# Adafruit_AD849x_Thermo.net
KiCad netlist of a schematic drawn in EAGLE
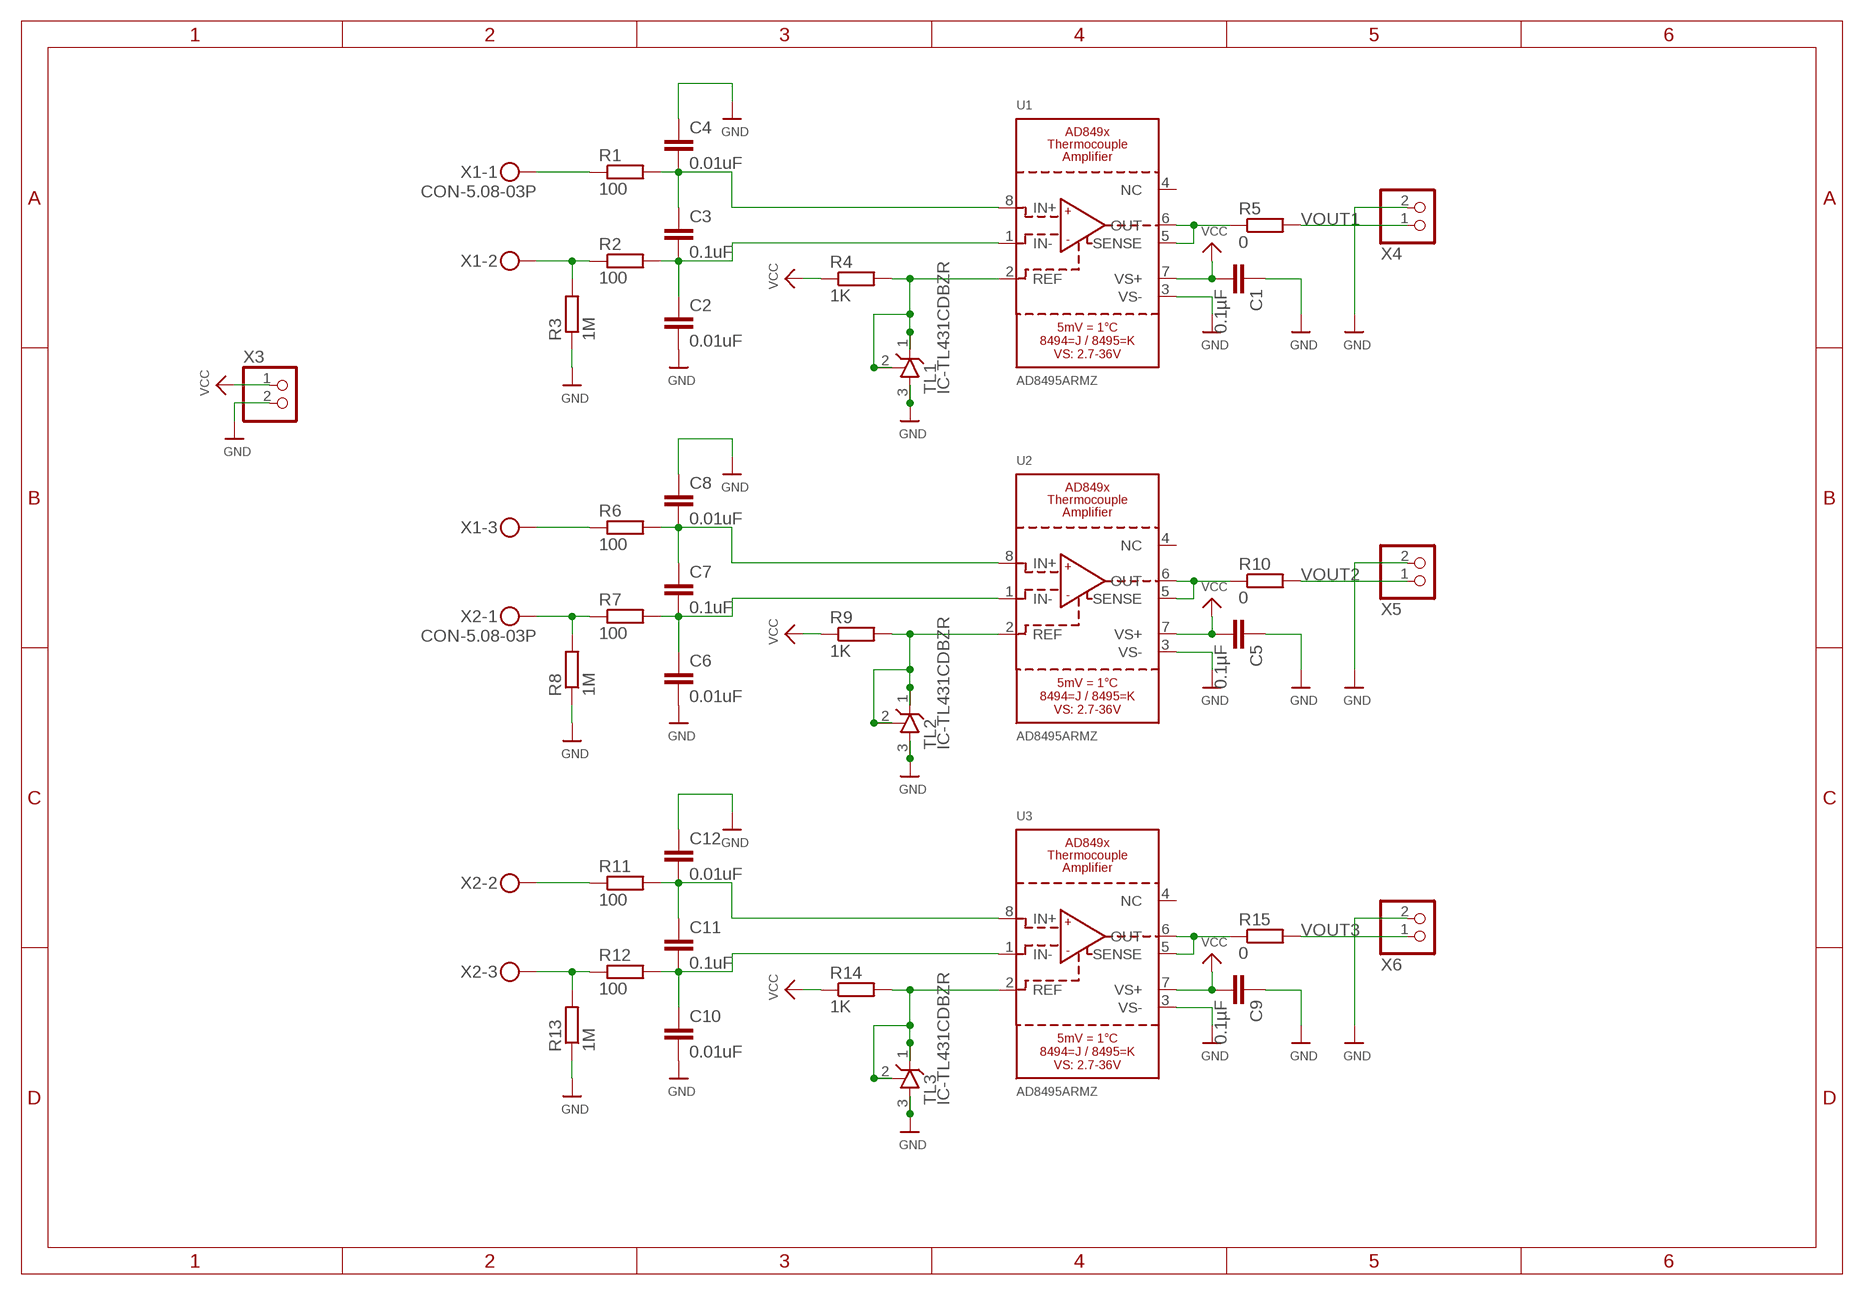
[diagram p0: schematic, sheet 1]

(export (version "E")
  (design (tool "Eeschema 10.0.6"))
  (components
    (comp (ref "C1")
      (value "0.1µF")
      (footprint "eagle-import:C0805")
      (libsource (lib "eagle-import") (part "CAP_0805"))
    )
    (comp (ref "C2")
      (value "0.01uF")
      (footprint "eagle-import:C0805")
      (libsource (lib "eagle-import") (part "CAP_0805"))
    )
    (comp (ref "C3")
      (value "0.1uF")
      (footprint "eagle-import:C0805")
      (libsource (lib "eagle-import") (part "CAP_0805"))
    )
    (comp (ref "C4")
      (value "0.01uF")
      (footprint "eagle-import:C0805")
      (libsource (lib "eagle-import") (part "CAP_0805"))
    )
    (comp (ref "C5")
      (value "0.1µF")
      (footprint "eagle-import:C0805")
      (libsource (lib "eagle-import") (part "CAP_0805"))
    )
    (comp (ref "C6")
      (value "0.01uF")
      (footprint "eagle-import:C0805")
      (libsource (lib "eagle-import") (part "CAP_0805"))
    )
    (comp (ref "C7")
      (value "0.1uF")
      (footprint "eagle-import:C0805")
      (libsource (lib "eagle-import") (part "CAP_0805"))
    )
    (comp (ref "C8")
      (value "0.01uF")
      (footprint "eagle-import:C0805")
      (libsource (lib "eagle-import") (part "CAP_0805"))
    )
    (comp (ref "C9")
      (value "0.1µF")
      (footprint "eagle-import:C0805")
      (libsource (lib "eagle-import") (part "CAP_0805"))
    )
    (comp (ref "C10")
      (value "0.01uF")
      (footprint "eagle-import:C0805")
      (libsource (lib "eagle-import") (part "CAP_0805"))
    )
    (comp (ref "C11")
      (value "0.1uF")
      (footprint "eagle-import:C0805")
      (libsource (lib "eagle-import") (part "CAP_0805"))
    )
    (comp (ref "C12")
      (value "0.01uF")
      (footprint "eagle-import:C0805")
      (libsource (lib "eagle-import") (part "CAP_0805"))
    )
    (comp (ref "R1")
      (value "100")
      (footprint "eagle-import:R0805")
      (libsource (lib "eagle-import") (part "R_0805"))
    )
    (comp (ref "R2")
      (value "100")
      (footprint "eagle-import:R0805")
      (libsource (lib "eagle-import") (part "R_0805"))
    )
    (comp (ref "R3")
      (value "1M")
      (footprint "eagle-import:R0805")
      (libsource (lib "eagle-import") (part "R_0805"))
    )
    (comp (ref "R4")
      (value "1K")
      (footprint "eagle-import:R0805")
      (libsource (lib "eagle-import") (part "R_0805"))
    )
    (comp (ref "R5")
      (value "0")
      (footprint "eagle-import:R0805")
      (libsource (lib "eagle-import") (part "R_0805"))
    )
    (comp (ref "R6")
      (value "100")
      (footprint "eagle-import:R0805")
      (libsource (lib "eagle-import") (part "R_0805"))
    )
    (comp (ref "R7")
      (value "100")
      (footprint "eagle-import:R0805")
      (libsource (lib "eagle-import") (part "R_0805"))
    )
    (comp (ref "R8")
      (value "1M")
      (footprint "eagle-import:R0805")
      (libsource (lib "eagle-import") (part "R_0805"))
    )
    (comp (ref "R9")
      (value "1K")
      (footprint "eagle-import:R0805")
      (libsource (lib "eagle-import") (part "R_0805"))
    )
    (comp (ref "R10")
      (value "0")
      (footprint "eagle-import:R0805")
      (libsource (lib "eagle-import") (part "R_0805"))
    )
    (comp (ref "R11")
      (value "100")
      (footprint "eagle-import:R0805")
      (libsource (lib "eagle-import") (part "R_0805"))
    )
    (comp (ref "R12")
      (value "100")
      (footprint "eagle-import:R0805")
      (libsource (lib "eagle-import") (part "R_0805"))
    )
    (comp (ref "R13")
      (value "1M")
      (footprint "eagle-import:R0805")
      (libsource (lib "eagle-import") (part "R_0805"))
    )
    (comp (ref "R14")
      (value "1K")
      (footprint "eagle-import:R0805")
      (libsource (lib "eagle-import") (part "R_0805"))
    )
    (comp (ref "R15")
      (value "0")
      (footprint "eagle-import:R0805")
      (libsource (lib "eagle-import") (part "R_0805"))
    )
    (comp (ref "TL1")
      (value "IC-TL431CDBZR")
      (footprint "eagle-import:SOT23")
      (libsource (lib "eagle-import") (part "IC-TL431CDBZR"))
    )
    (comp (ref "TL2")
      (value "IC-TL431CDBZR")
      (footprint "eagle-import:SOT23")
      (libsource (lib "eagle-import") (part "IC-TL431CDBZR"))
    )
    (comp (ref "TL3")
      (value "IC-TL431CDBZR")
      (footprint "eagle-import:SOT23")
      (libsource (lib "eagle-import") (part "IC-TL431CDBZR"))
    )
    (comp (ref "U1")
      (value "AD8495ARMZ")
      (footprint "eagle-import:MSOP8_0.65MM")
      (libsource (lib "eagle-import") (part "AD849X"))
    )
    (comp (ref "U2")
      (value "AD8495ARMZ")
      (footprint "eagle-import:MSOP8_0.65MM")
      (libsource (lib "eagle-import") (part "AD849X"))
    )
    (comp (ref "U3")
      (value "AD8495ARMZ")
      (footprint "eagle-import:MSOP8_0.65MM")
      (libsource (lib "eagle-import") (part "AD849X"))
    )
    (comp (ref "X1")
      (value "CON-5.08-03P")
      (footprint "eagle-import:MKDSN1,5_3-5,08")
      (libsource (lib "eagle-import") (part "CON-5.08-03P"))
    )
    (comp (ref "X2")
      (value "CON-5.08-03P")
      (footprint "eagle-import:MKDSN1,5_3-5,08")
      (libsource (lib "eagle-import") (part "CON-5.08-03P"))
    )
    (comp (ref "X3")
      (value "CON-CP-02")
      (footprint "eagle-import:CON-CT-02")
      (libsource (lib "eagle-import") (part "CON-CP-02"))
    )
    (comp (ref "X4")
      (value "CON-CP-02")
      (footprint "eagle-import:CON-CT-02")
      (libsource (lib "eagle-import") (part "CON-CP-02"))
    )
    (comp (ref "X5")
      (value "CON-CP-02")
      (footprint "eagle-import:CON-CT-02")
      (libsource (lib "eagle-import") (part "CON-CP-02"))
    )
    (comp (ref "X6")
      (value "CON-CP-02")
      (footprint "eagle-import:CON-CT-02")
      (libsource (lib "eagle-import") (part "CON-CP-02"))
    )
  )
  (nets
    (net (code "1") (name "/VOUT1") (class "Default")
      (node (ref "R5") (pin "1") (pinfunction "1_1") (pintype "passive"))
      (node (ref "U1") (pin "5") (pinfunction "SENSE_5") (pintype "bidirectional"))
      (node (ref "U1") (pin "6") (pinfunction "OUT_6") (pintype "output"))
    )
    (net (code "2") (name "/VOUT2") (class "Default")
      (node (ref "R10") (pin "1") (pinfunction "1_1") (pintype "passive"))
      (node (ref "U2") (pin "5") (pinfunction "SENSE_5") (pintype "bidirectional"))
      (node (ref "U2") (pin "6") (pinfunction "OUT_6") (pintype "output"))
    )
    (net (code "3") (name "/VOUT3") (class "Default")
      (node (ref "R15") (pin "1") (pinfunction "1_1") (pintype "passive"))
      (node (ref "U3") (pin "5") (pinfunction "SENSE_5") (pintype "bidirectional"))
      (node (ref "U3") (pin "6") (pinfunction "OUT_6") (pintype "output"))
    )
    (net (code "4") (name "GND") (class "Default")
      (node (ref "C1") (pin "1") (pinfunction "1_1") (pintype "passive"))
      (node (ref "C10") (pin "2") (pinfunction "2_2") (pintype "passive"))
      (node (ref "C12") (pin "1") (pinfunction "1_1") (pintype "passive"))
      (node (ref "C2") (pin "2") (pinfunction "2_2") (pintype "passive"))
      (node (ref "C4") (pin "1") (pinfunction "1_1") (pintype "passive"))
      (node (ref "C5") (pin "1") (pinfunction "1_1") (pintype "passive"))
      (node (ref "C6") (pin "2") (pinfunction "2_2") (pintype "passive"))
      (node (ref "C8") (pin "1") (pinfunction "1_1") (pintype "passive"))
      (node (ref "C9") (pin "1") (pinfunction "1_1") (pintype "passive"))
      (node (ref "R13") (pin "1") (pinfunction "1_1") (pintype "passive"))
      (node (ref "R3") (pin "1") (pinfunction "1_1") (pintype "passive"))
      (node (ref "R8") (pin "1") (pinfunction "1_1") (pintype "passive"))
      (node (ref "TL1") (pin "3") (pinfunction "A_3") (pintype "passive"))
      (node (ref "TL2") (pin "3") (pinfunction "A_3") (pintype "passive"))
      (node (ref "TL3") (pin "3") (pinfunction "A_3") (pintype "passive"))
      (node (ref "U1") (pin "3") (pinfunction "VS-_3") (pintype "power_in"))
      (node (ref "U2") (pin "3") (pinfunction "VS-_3") (pintype "power_in"))
      (node (ref "U3") (pin "3") (pinfunction "VS-_3") (pintype "power_in"))
      (node (ref "X3") (pin "2") (pinfunction "2_2") (pintype "passive"))
      (node (ref "X4") (pin "2") (pinfunction "2_2") (pintype "passive"))
      (node (ref "X5") (pin "2") (pinfunction "2_2") (pintype "passive"))
      (node (ref "X6") (pin "2") (pinfunction "2_2") (pintype "passive"))
    )
    (net (code "5") (name "Net-(R5-Pad2)") (class "Default")
      (node (ref "R5") (pin "2") (pinfunction "2_2") (pintype "passive"))
      (node (ref "X4") (pin "1") (pinfunction "1_1") (pintype "passive"))
    )
    (net (code "6") (name "Net-(R10-Pad2)") (class "Default")
      (node (ref "R10") (pin "2") (pinfunction "2_2") (pintype "passive"))
      (node (ref "X5") (pin "1") (pinfunction "1_1") (pintype "passive"))
    )
    (net (code "7") (name "Net-(R15-Pad2)") (class "Default")
      (node (ref "R15") (pin "2") (pinfunction "2_2") (pintype "passive"))
      (node (ref "X6") (pin "1") (pinfunction "1_1") (pintype "passive"))
    )
    (net (code "8") (name "Net-(TL1-C)") (class "Default")
      (node (ref "R4") (pin "2") (pinfunction "2_2") (pintype "passive"))
      (node (ref "TL1") (pin "1") (pinfunction "C_1") (pintype "passive"))
      (node (ref "TL1") (pin "2") (pinfunction "R_2") (pintype "passive"))
      (node (ref "U1") (pin "2") (pinfunction "REF_2") (pintype "input"))
    )
    (net (code "9") (name "Net-(TL2-C)") (class "Default")
      (node (ref "R9") (pin "2") (pinfunction "2_2") (pintype "passive"))
      (node (ref "TL2") (pin "1") (pinfunction "C_1") (pintype "passive"))
      (node (ref "TL2") (pin "2") (pinfunction "R_2") (pintype "passive"))
      (node (ref "U2") (pin "2") (pinfunction "REF_2") (pintype "input"))
    )
    (net (code "10") (name "Net-(TL3-C)") (class "Default")
      (node (ref "R14") (pin "2") (pinfunction "2_2") (pintype "passive"))
      (node (ref "TL3") (pin "1") (pinfunction "C_1") (pintype "passive"))
      (node (ref "TL3") (pin "2") (pinfunction "R_2") (pintype "passive"))
      (node (ref "U3") (pin "2") (pinfunction "REF_2") (pintype "input"))
    )
    (net (code "11") (name "Net-(U1-IN+)") (class "Default")
      (node (ref "C3") (pin "1") (pinfunction "1_1") (pintype "passive"))
      (node (ref "C4") (pin "2") (pinfunction "2_2") (pintype "passive"))
      (node (ref "R1") (pin "2") (pinfunction "2_2") (pintype "passive"))
      (node (ref "U1") (pin "8") (pinfunction "IN+_8") (pintype "input"))
    )
    (net (code "12") (name "Net-(U1-IN-)") (class "Default")
      (node (ref "C2") (pin "1") (pinfunction "1_1") (pintype "passive"))
      (node (ref "C3") (pin "2") (pinfunction "2_2") (pintype "passive"))
      (node (ref "R2") (pin "2") (pinfunction "2_2") (pintype "passive"))
      (node (ref "U1") (pin "1") (pinfunction "IN-_1") (pintype "input"))
    )
    (net (code "13") (name "Net-(U2-IN+)") (class "Default")
      (node (ref "C7") (pin "1") (pinfunction "1_1") (pintype "passive"))
      (node (ref "C8") (pin "2") (pinfunction "2_2") (pintype "passive"))
      (node (ref "R6") (pin "2") (pinfunction "2_2") (pintype "passive"))
      (node (ref "U2") (pin "8") (pinfunction "IN+_8") (pintype "input"))
    )
    (net (code "14") (name "Net-(U2-IN-)") (class "Default")
      (node (ref "C6") (pin "1") (pinfunction "1_1") (pintype "passive"))
      (node (ref "C7") (pin "2") (pinfunction "2_2") (pintype "passive"))
      (node (ref "R7") (pin "2") (pinfunction "2_2") (pintype "passive"))
      (node (ref "U2") (pin "1") (pinfunction "IN-_1") (pintype "input"))
    )
    (net (code "15") (name "Net-(U3-IN+)") (class "Default")
      (node (ref "C11") (pin "1") (pinfunction "1_1") (pintype "passive"))
      (node (ref "C12") (pin "2") (pinfunction "2_2") (pintype "passive"))
      (node (ref "R11") (pin "2") (pinfunction "2_2") (pintype "passive"))
      (node (ref "U3") (pin "8") (pinfunction "IN+_8") (pintype "input"))
    )
    (net (code "16") (name "Net-(U3-IN-)") (class "Default")
      (node (ref "C10") (pin "1") (pinfunction "1_1") (pintype "passive"))
      (node (ref "C11") (pin "2") (pinfunction "2_2") (pintype "passive"))
      (node (ref "R12") (pin "2") (pinfunction "2_2") (pintype "passive"))
      (node (ref "U3") (pin "1") (pinfunction "IN-_1") (pintype "input"))
    )
    (net (code "17") (name "Net-(X1A-KL)") (class "Default")
      (node (ref "R1") (pin "1") (pinfunction "1_1") (pintype "passive"))
      (node (ref "X1") (pin "1") (pinfunction "KL_1") (pintype "passive"))
    )
    (net (code "18") (name "Net-(X1B-KL)") (class "Default")
      (node (ref "R2") (pin "1") (pinfunction "1_1") (pintype "passive"))
      (node (ref "R3") (pin "2") (pinfunction "2_2") (pintype "passive"))
      (node (ref "X1") (pin "2") (pinfunction "KL_2") (pintype "passive"))
    )
    (net (code "19") (name "Net-(X1C-KL)") (class "Default")
      (node (ref "R6") (pin "1") (pinfunction "1_1") (pintype "passive"))
      (node (ref "X1") (pin "3") (pinfunction "KL_3") (pintype "passive"))
    )
    (net (code "20") (name "Net-(X2A-KL)") (class "Default")
      (node (ref "R7") (pin "1") (pinfunction "1_1") (pintype "passive"))
      (node (ref "R8") (pin "2") (pinfunction "2_2") (pintype "passive"))
      (node (ref "X2") (pin "1") (pinfunction "KL_1") (pintype "passive"))
    )
    (net (code "21") (name "Net-(X2B-KL)") (class "Default")
      (node (ref "R11") (pin "1") (pinfunction "1_1") (pintype "passive"))
      (node (ref "X2") (pin "2") (pinfunction "KL_2") (pintype "passive"))
    )
    (net (code "22") (name "Net-(X2C-KL)") (class "Default")
      (node (ref "R12") (pin "1") (pinfunction "1_1") (pintype "passive"))
      (node (ref "R13") (pin "2") (pinfunction "2_2") (pintype "passive"))
      (node (ref "X2") (pin "3") (pinfunction "KL_3") (pintype "passive"))
    )
    (net (code "23") (name "VCC") (class "Default")
      (node (ref "C1") (pin "2") (pinfunction "2_2") (pintype "passive"))
      (node (ref "C5") (pin "2") (pinfunction "2_2") (pintype "passive"))
      (node (ref "C9") (pin "2") (pinfunction "2_2") (pintype "passive"))
      (node (ref "R14") (pin "1") (pinfunction "1_1") (pintype "passive"))
      (node (ref "R4") (pin "1") (pinfunction "1_1") (pintype "passive"))
      (node (ref "R9") (pin "1") (pinfunction "1_1") (pintype "passive"))
      (node (ref "U1") (pin "7") (pinfunction "VS+_7") (pintype "power_in"))
      (node (ref "U2") (pin "7") (pinfunction "VS+_7") (pintype "power_in"))
      (node (ref "U3") (pin "7") (pinfunction "VS+_7") (pintype "power_in"))
      (node (ref "X3") (pin "1") (pinfunction "1_1") (pintype "passive"))
    )
    (net (code "24") (name "unconnected-(U1-NC-Pad4)") (class "Default")
      (node (ref "U1") (pin "4") (pinfunction "NC_4") (pintype "no_connect"))
    )
    (net (code "25") (name "unconnected-(U2-NC-Pad4)") (class "Default")
      (node (ref "U2") (pin "4") (pinfunction "NC_4") (pintype "no_connect"))
    )
    (net (code "26") (name "unconnected-(U3-NC-Pad4)") (class "Default")
      (node (ref "U3") (pin "4") (pinfunction "NC_4") (pintype "no_connect"))
    )
  )
)
